# ESP12Proto-V1_0.net
KiCad netlist of a schematic drawn in EAGLE
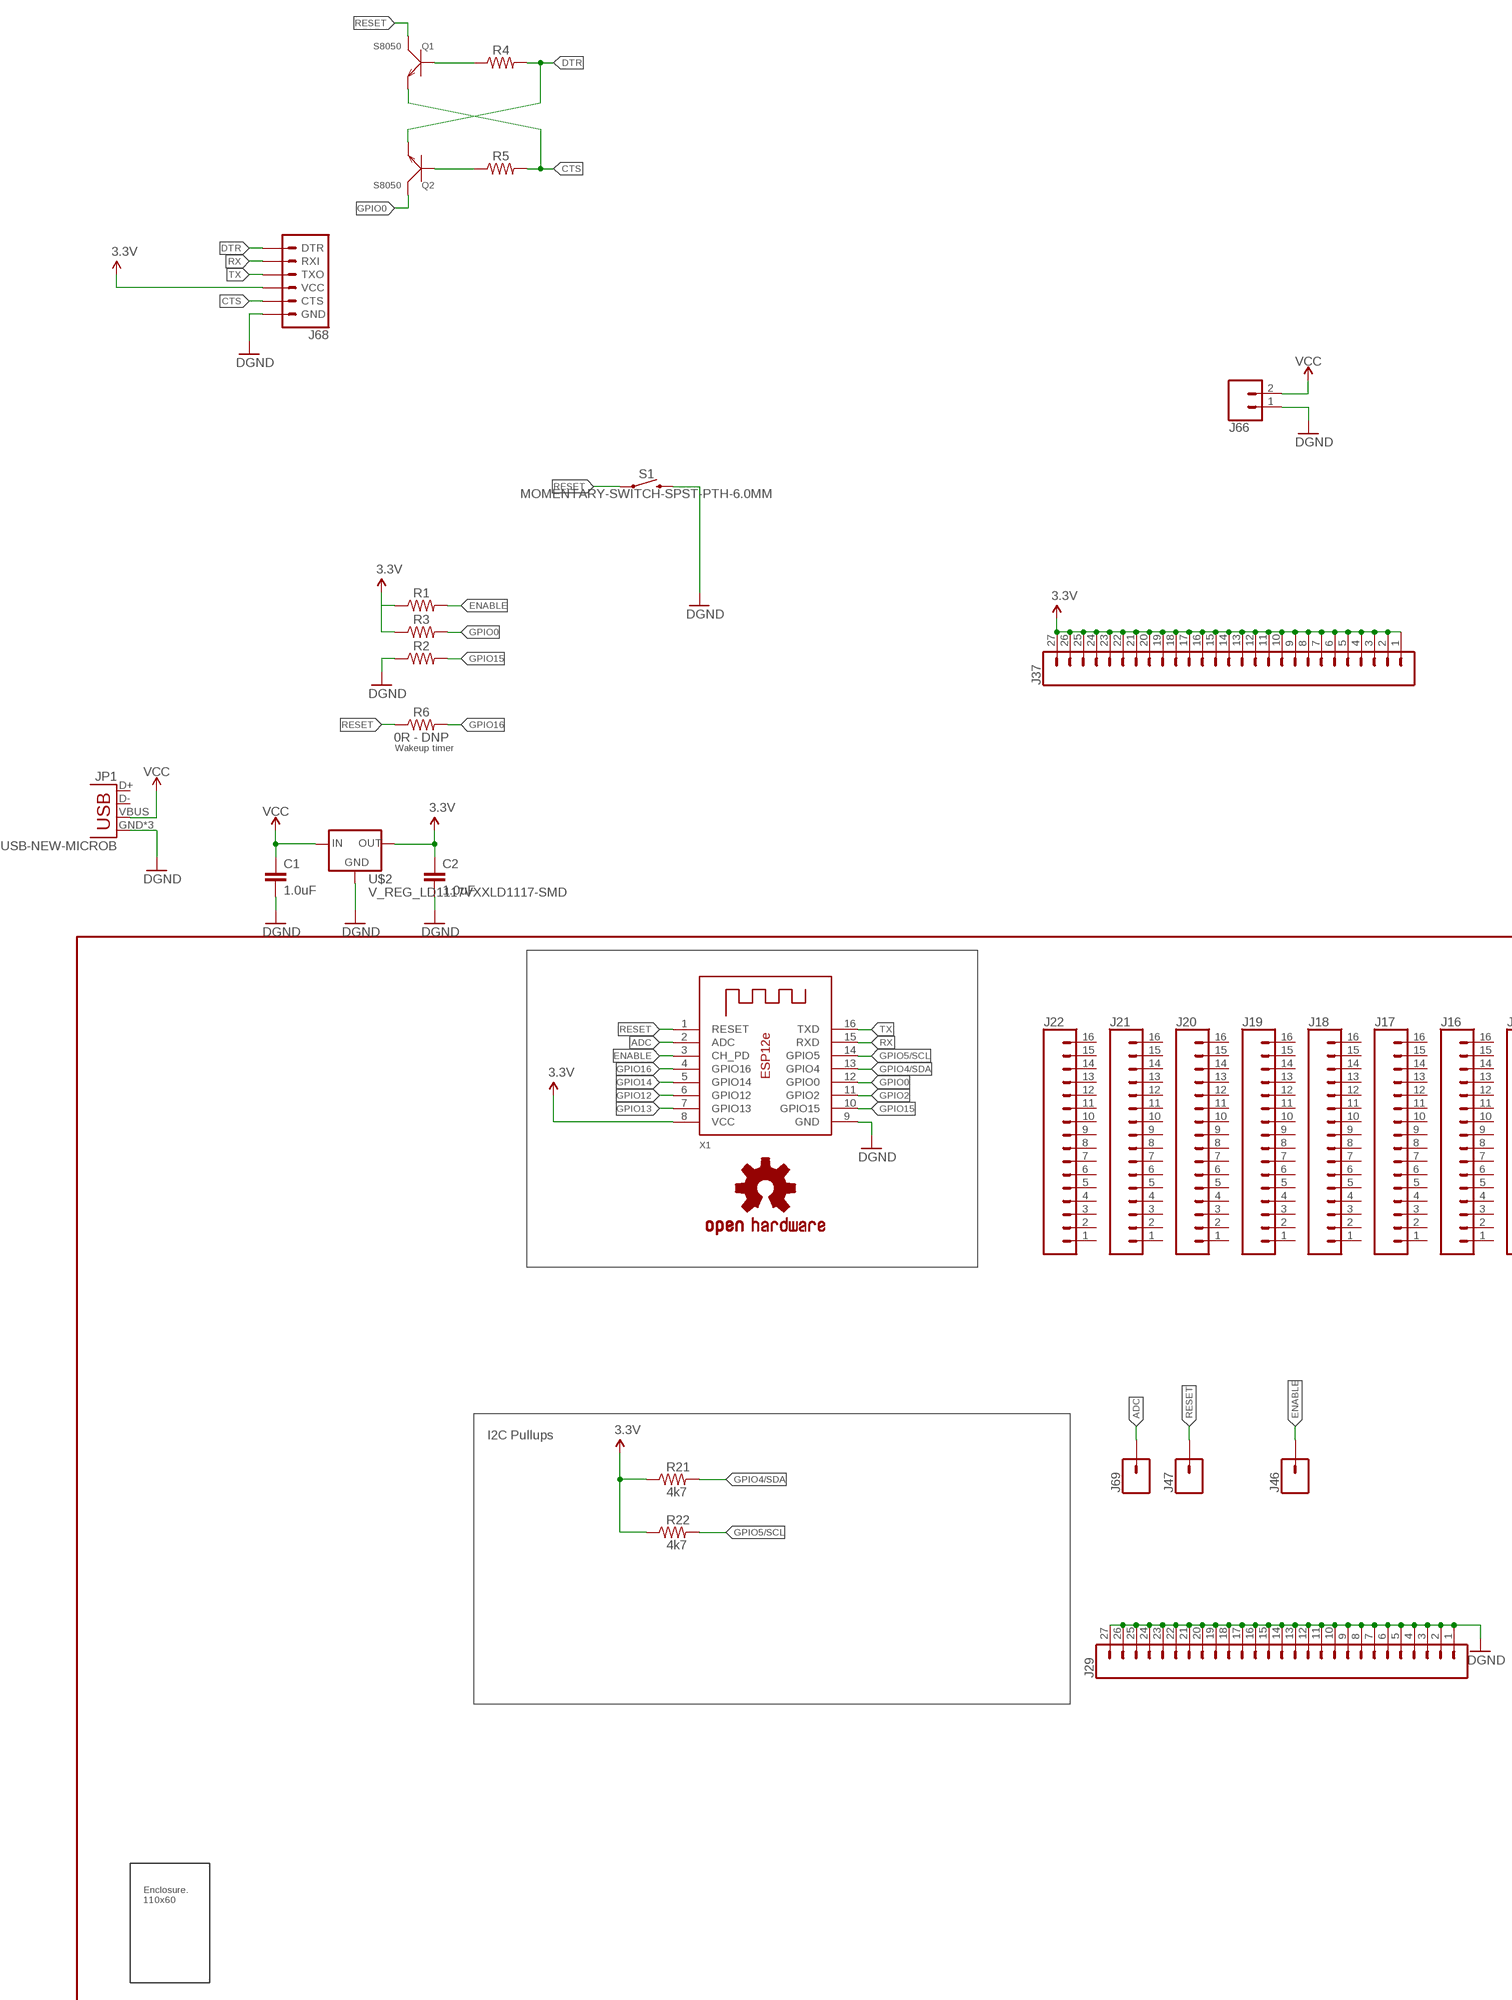
[diagram p0: schematic, sheet 1, part 1 of 2]
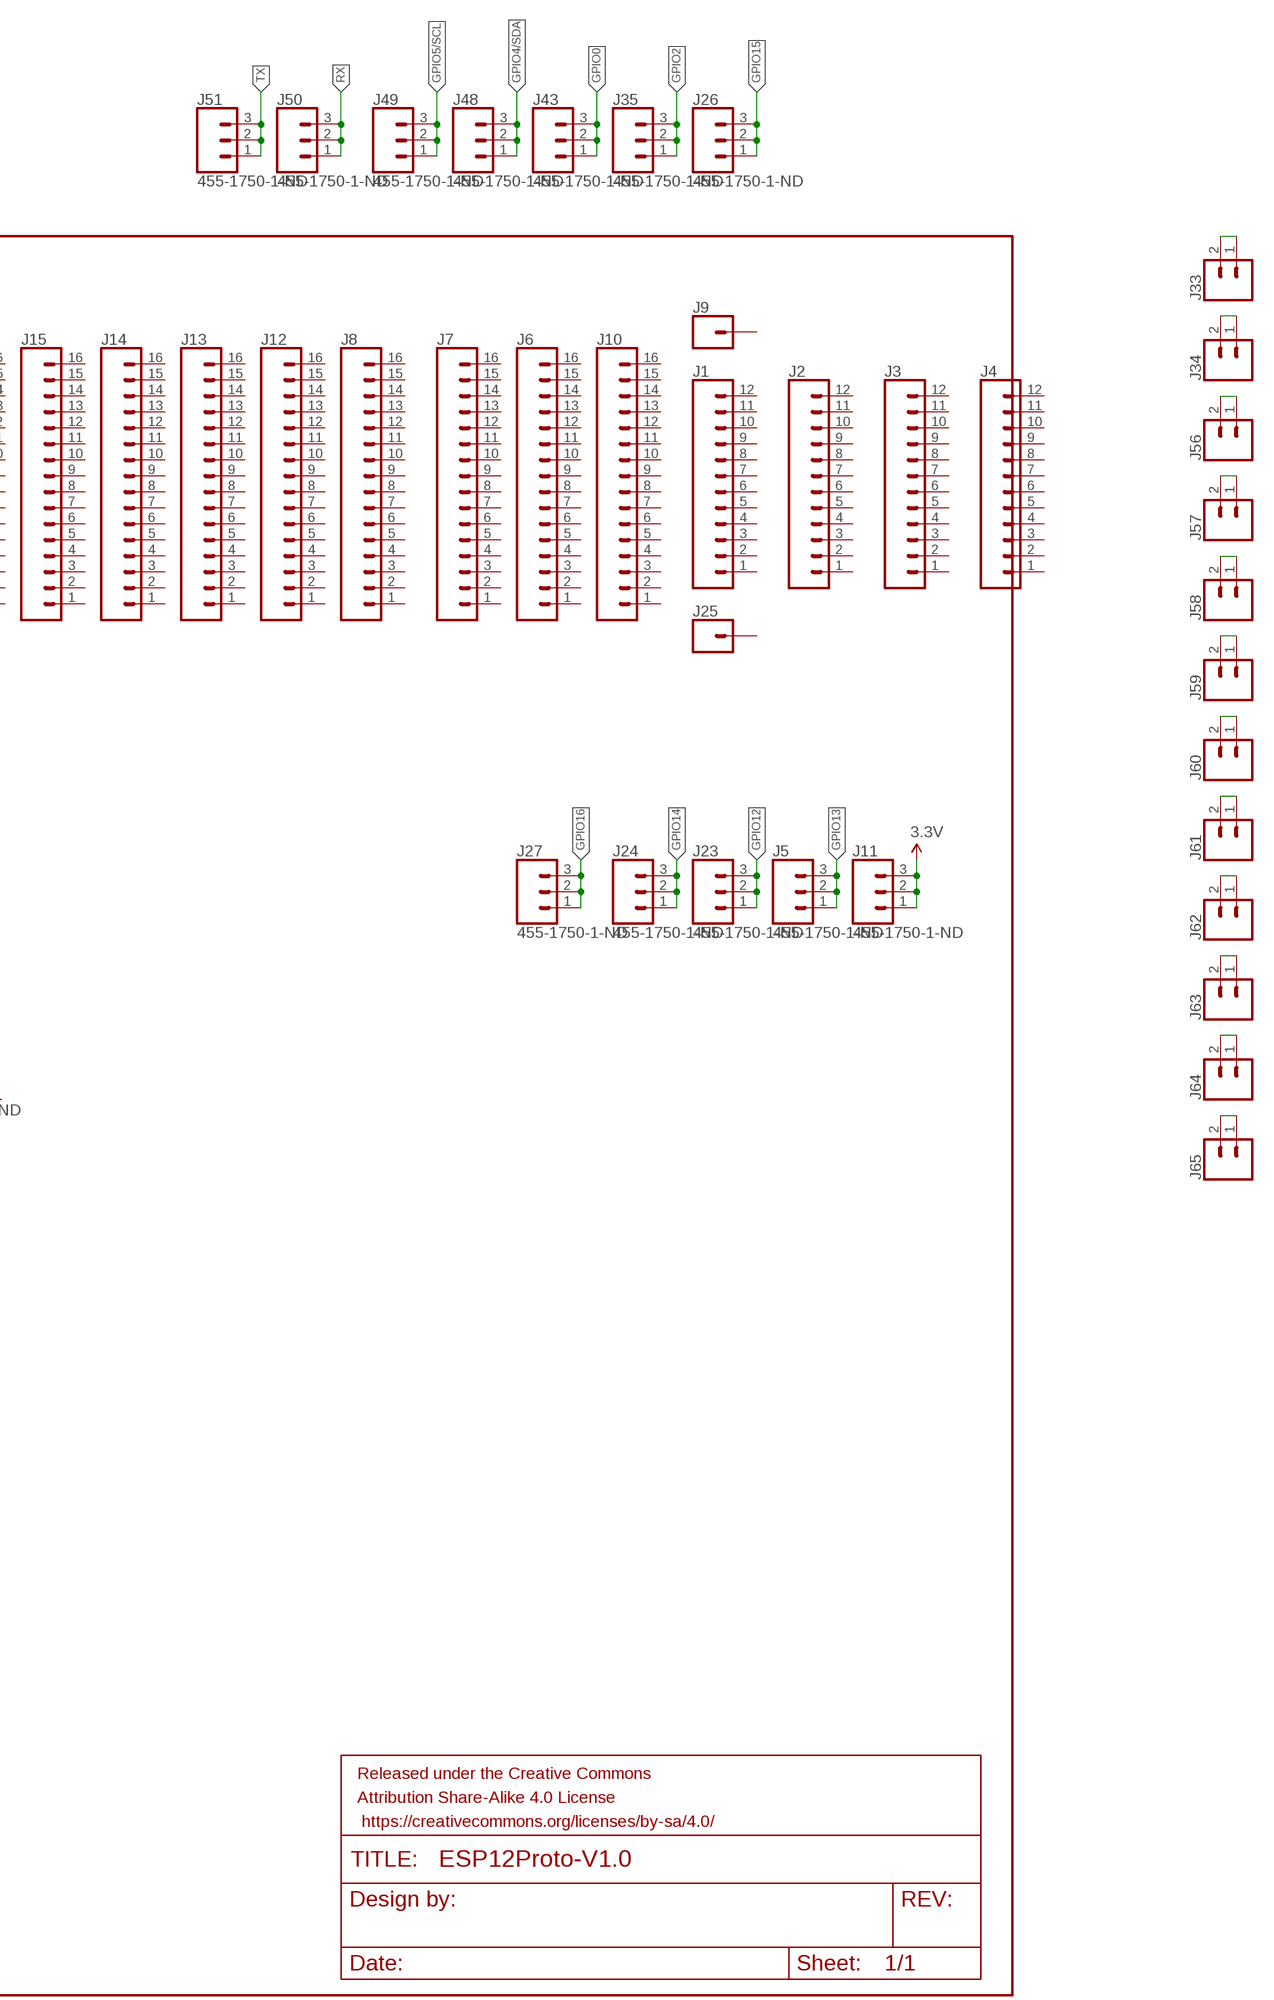
[diagram p1: schematic, sheet 1, part 2 of 2]

(export (version "E")
  (design (tool "Eeschema 10.0.6"))
  (components
    (comp (ref "C1")
      (value "1.0uF")
      (footprint "eagle-import:0805")
      (libsource (lib "eagle-import") (part "1.0UF-0805-25V-10%"))
    )
    (comp (ref "C2")
      (value "1.0uF")
      (footprint "eagle-import:0805")
      (libsource (lib "eagle-import") (part "1.0UF-0805-25V-10%"))
    )
    (comp (ref "FRAME2")
      (value "FRAME-LEDGER")
      (footprint "eagle-import:CREATIVE_COMMONS")
      (libsource (lib "eagle-import") (part "FRAME-LEDGER"))
    )
    (comp (ref "J1")
      (value "CONN_12NO_SILK")
      (footprint "eagle-import:1X12_NO_SILK")
      (libsource (lib "eagle-import") (part "CONN_12NO_SILK"))
    )
    (comp (ref "J2")
      (value "CONN_12NO_SILK")
      (footprint "eagle-import:1X12_NO_SILK")
      (libsource (lib "eagle-import") (part "CONN_12NO_SILK"))
    )
    (comp (ref "J3")
      (value "CONN_12NO_SILK")
      (footprint "eagle-import:1X12_NO_SILK")
      (libsource (lib "eagle-import") (part "CONN_12NO_SILK"))
    )
    (comp (ref "J4")
      (value "CONN_12NO_SILK")
      (footprint "eagle-import:1X12_NO_SILK")
      (libsource (lib "eagle-import") (part "CONN_12NO_SILK"))
    )
    (comp (ref "J5")
      (value "455-1750-1-ND")
      (footprint "eagle-import:1X03")
      (libsource (lib "eagle-import") (part "CONN_03"))
    )
    (comp (ref "J6")
      (value "CONN_161X16_NO_SILK")
      (footprint "eagle-import:1X16_NO_SILK")
      (libsource (lib "eagle-import") (part "CONN_161X16_NO_SILK"))
    )
    (comp (ref "J7")
      (value "CONN_161X16_NO_SILK")
      (footprint "eagle-import:1X16_NO_SILK")
      (libsource (lib "eagle-import") (part "CONN_161X16_NO_SILK"))
    )
    (comp (ref "J8")
      (value "CONN_161X16_NO_SILK")
      (footprint "eagle-import:1X16_NO_SILK")
      (libsource (lib "eagle-import") (part "CONN_161X16_NO_SILK"))
    )
    (comp (ref "J9")
      (value "CONN_01PTH_NO_SILK_YES_STOP")
      (footprint "eagle-import:1X01_NO_SILK")
      (libsource (lib "eagle-import") (part "CONN_01PTH_NO_SILK_YES_STOP"))
    )
    (comp (ref "J10")
      (value "CONN_161X16_NO_SILK")
      (footprint "eagle-import:1X16_NO_SILK")
      (libsource (lib "eagle-import") (part "CONN_161X16_NO_SILK"))
    )
    (comp (ref "J11")
      (value "455-1750-1-ND")
      (footprint "eagle-import:1X03")
      (libsource (lib "eagle-import") (part "CONN_03"))
    )
    (comp (ref "J12")
      (value "CONN_161X16_NO_SILK")
      (footprint "eagle-import:1X16_NO_SILK")
      (libsource (lib "eagle-import") (part "CONN_161X16_NO_SILK"))
    )
    (comp (ref "J13")
      (value "CONN_161X16_NO_SILK")
      (footprint "eagle-import:1X16_NO_SILK")
      (libsource (lib "eagle-import") (part "CONN_161X16_NO_SILK"))
    )
    (comp (ref "J14")
      (value "CONN_161X16_NO_SILK")
      (footprint "eagle-import:1X16_NO_SILK")
      (libsource (lib "eagle-import") (part "CONN_161X16_NO_SILK"))
    )
    (comp (ref "J15")
      (value "CONN_161X16_NO_SILK")
      (footprint "eagle-import:1X16_NO_SILK")
      (libsource (lib "eagle-import") (part "CONN_161X16_NO_SILK"))
    )
    (comp (ref "J16")
      (value "CONN_161X16_NO_SILK")
      (footprint "eagle-import:1X16_NO_SILK")
      (libsource (lib "eagle-import") (part "CONN_161X16_NO_SILK"))
    )
    (comp (ref "J17")
      (value "CONN_161X16_NO_SILK")
      (footprint "eagle-import:1X16_NO_SILK")
      (libsource (lib "eagle-import") (part "CONN_161X16_NO_SILK"))
    )
    (comp (ref "J18")
      (value "CONN_161X16_NO_SILK")
      (footprint "eagle-import:1X16_NO_SILK")
      (libsource (lib "eagle-import") (part "CONN_161X16_NO_SILK"))
    )
    (comp (ref "J19")
      (value "CONN_161X16_NO_SILK")
      (footprint "eagle-import:1X16_NO_SILK")
      (libsource (lib "eagle-import") (part "CONN_161X16_NO_SILK"))
    )
    (comp (ref "J20")
      (value "CONN_161X16_NO_SILK")
      (footprint "eagle-import:1X16_NO_SILK")
      (libsource (lib "eagle-import") (part "CONN_161X16_NO_SILK"))
    )
    (comp (ref "J21")
      (value "CONN_161X16_NO_SILK")
      (footprint "eagle-import:1X16_NO_SILK")
      (libsource (lib "eagle-import") (part "CONN_161X16_NO_SILK"))
    )
    (comp (ref "J22")
      (value "CONN_161X16_NO_SILK")
      (footprint "eagle-import:1X16_NO_SILK")
      (libsource (lib "eagle-import") (part "CONN_161X16_NO_SILK"))
    )
    (comp (ref "J23")
      (value "455-1750-1-ND")
      (footprint "eagle-import:1X03")
      (libsource (lib "eagle-import") (part "CONN_03"))
    )
    (comp (ref "J24")
      (value "455-1750-1-ND")
      (footprint "eagle-import:1X03")
      (libsource (lib "eagle-import") (part "CONN_03"))
    )
    (comp (ref "J25")
      (value "CONN_01PTH_NO_SILK_YES_STOP")
      (footprint "eagle-import:1X01_NO_SILK")
      (libsource (lib "eagle-import") (part "CONN_01PTH_NO_SILK_YES_STOP"))
    )
    (comp (ref "J26")
      (value "455-1750-1-ND")
      (footprint "eagle-import:1X03")
      (libsource (lib "eagle-import") (part "CONN_03"))
    )
    (comp (ref "J27")
      (value "455-1750-1-ND")
      (footprint "eagle-import:1X03")
      (libsource (lib "eagle-import") (part "CONN_03"))
    )
    (comp (ref "J29")
      (value "CONN_27")
      (footprint "eagle-import:1X27")
      (libsource (lib "eagle-import") (part "CONN_27"))
    )
    (comp (ref "J33")
      (value "CONN_02")
      (footprint "eagle-import:1X02")
      (libsource (lib "eagle-import") (part "CONN_02"))
    )
    (comp (ref "J34")
      (value "CONN_02")
      (footprint "eagle-import:1X02")
      (libsource (lib "eagle-import") (part "CONN_02"))
    )
    (comp (ref "J35")
      (value "455-1750-1-ND")
      (footprint "eagle-import:1X03")
      (libsource (lib "eagle-import") (part "CONN_03"))
    )
    (comp (ref "J37")
      (value "CONN_27")
      (footprint "eagle-import:1X27")
      (libsource (lib "eagle-import") (part "CONN_27"))
    )
    (comp (ref "J43")
      (value "455-1750-1-ND")
      (footprint "eagle-import:1X03")
      (libsource (lib "eagle-import") (part "CONN_03"))
    )
    (comp (ref "J46")
      (value "CONN_01PTH_NO_SILK_YES_STOP")
      (footprint "eagle-import:1X01_NO_SILK")
      (libsource (lib "eagle-import") (part "CONN_01PTH_NO_SILK_YES_STOP"))
    )
    (comp (ref "J47")
      (value "CONN_01PTH_NO_SILK_YES_STOP")
      (footprint "eagle-import:1X01_NO_SILK")
      (libsource (lib "eagle-import") (part "CONN_01PTH_NO_SILK_YES_STOP"))
    )
    (comp (ref "J48")
      (value "455-1750-1-ND")
      (footprint "eagle-import:1X03")
      (libsource (lib "eagle-import") (part "CONN_03"))
    )
    (comp (ref "J49")
      (value "455-1750-1-ND")
      (footprint "eagle-import:1X03")
      (libsource (lib "eagle-import") (part "CONN_03"))
    )
    (comp (ref "J50")
      (value "455-1750-1-ND")
      (footprint "eagle-import:1X03")
      (libsource (lib "eagle-import") (part "CONN_03"))
    )
    (comp (ref "J51")
      (value "455-1750-1-ND")
      (footprint "eagle-import:1X03")
      (libsource (lib "eagle-import") (part "CONN_03"))
    )
    (comp (ref "J56")
      (value "CONN_02")
      (footprint "eagle-import:1X02")
      (libsource (lib "eagle-import") (part "CONN_02"))
    )
    (comp (ref "J57")
      (value "CONN_02")
      (footprint "eagle-import:1X02")
      (libsource (lib "eagle-import") (part "CONN_02"))
    )
    (comp (ref "J58")
      (value "CONN_02")
      (footprint "eagle-import:1X02")
      (libsource (lib "eagle-import") (part "CONN_02"))
    )
    (comp (ref "J59")
      (value "CONN_02")
      (footprint "eagle-import:1X02")
      (libsource (lib "eagle-import") (part "CONN_02"))
    )
    (comp (ref "J60")
      (value "CONN_02")
      (footprint "eagle-import:1X02")
      (libsource (lib "eagle-import") (part "CONN_02"))
    )
    (comp (ref "J61")
      (value "CONN_02")
      (footprint "eagle-import:1X02")
      (libsource (lib "eagle-import") (part "CONN_02"))
    )
    (comp (ref "J62")
      (value "CONN_02")
      (footprint "eagle-import:1X02")
      (libsource (lib "eagle-import") (part "CONN_02"))
    )
    (comp (ref "J63")
      (value "CONN_02")
      (footprint "eagle-import:1X02")
      (libsource (lib "eagle-import") (part "CONN_02"))
    )
    (comp (ref "J64")
      (value "CONN_02")
      (footprint "eagle-import:1X02")
      (libsource (lib "eagle-import") (part "CONN_02"))
    )
    (comp (ref "J65")
      (value "CONN_02")
      (footprint "eagle-import:1X02")
      (libsource (lib "eagle-import") (part "CONN_02"))
    )
    (comp (ref "J66")
      (value "CONN_02-JST-2MM-SMT")
      (footprint "eagle-import:JST-2-SMD")
      (libsource (lib "eagle-import") (part "CONN_02-JST-2MM-SMT"))
    )
    (comp (ref "J68")
      (value "6_PIN_SERIAL_TARGETSILK")
      (footprint "eagle-import:6_PIN_SERIAL_TARGET_SIDE_W_SILK")
      (libsource (lib "eagle-import") (part "6_PIN_SERIAL_TARGETSILK"))
    )
    (comp (ref "J69")
      (value "CONN_01PTH_NO_SILK_YES_STOP")
      (footprint "eagle-import:1X01_NO_SILK")
      (libsource (lib "eagle-import") (part "CONN_01PTH_NO_SILK_YES_STOP"))
    )
    (comp (ref "JP1")
      (value "USB-NEW-MICROB")
      (footprint "eagle-import:USB-MICROB")
      (libsource (lib "eagle-import") (part "USB-NEW-MICROB"))
    )
    (comp (ref "LOGO1")
      (value "OSHW-LOGOM")
      (footprint "eagle-import:OSHW-LOGO-M")
      (libsource (lib "eagle-import") (part "OSHW-LOGOM"))
    )
    (comp (ref "Q1")
      (value "S8050")
      (footprint "eagle-import:SOT-23")
      (libsource (lib "eagle-import") (part "SMD-TRANSISTORS-NPN-25V-500MW-S8050(SOT-23)"))
    )
    (comp (ref "Q2")
      (value "S8050")
      (footprint "eagle-import:SOT-23")
      (libsource (lib "eagle-import") (part "SMD-TRANSISTORS-NPN-25V-500MW-S8050(SOT-23)"))
    )
    (comp (ref "R1")
      (value "RESISTOR0805")
      (footprint "eagle-import:0805")
      (libsource (lib "eagle-import") (part "RESISTOR0805"))
    )
    (comp (ref "R2")
      (value "RESISTOR0805")
      (footprint "eagle-import:0805")
      (libsource (lib "eagle-import") (part "RESISTOR0805"))
    )
    (comp (ref "R3")
      (value "RESISTOR0805")
      (footprint "eagle-import:0805")
      (libsource (lib "eagle-import") (part "RESISTOR0805"))
    )
    (comp (ref "R4")
      (value "RESISTOR0805")
      (footprint "eagle-import:0805")
      (libsource (lib "eagle-import") (part "RESISTOR0805"))
    )
    (comp (ref "R5")
      (value "RESISTOR0805")
      (footprint "eagle-import:0805")
      (libsource (lib "eagle-import") (part "RESISTOR0805"))
    )
    (comp (ref "R6")
      (value "0R - DNP")
      (footprint "eagle-import:0805")
      (libsource (lib "eagle-import") (part "RESISTOR0805"))
    )
    (comp (ref "R21")
      (value "4k7")
      (footprint "eagle-import:0805")
      (libsource (lib "eagle-import") (part "RESISTOR0805"))
    )
    (comp (ref "R22")
      (value "4k7")
      (footprint "eagle-import:0805")
      (libsource (lib "eagle-import") (part "RESISTOR0805"))
    )
    (comp (ref "S1")
      (value "MOMENTARY-SWITCH-SPST-PTH-6.0MM")
      (footprint "eagle-import:TACTILE_SWITCH_PTH_6.0MM")
      (libsource (lib "eagle-import") (part "MOMENTARY-SWITCH-SPST-PTH-6.0MM"))
    )
    (comp (ref "U$1")
      (value "CAMDENBOSS-ENCLOSURE-110X60BOTH-EXTENDED-WIDE")
      (footprint "eagle-import:CAMDENBOSS_ENCLOSURE_110X60_WIDE_EXTENDED")
      (libsource (lib "eagle-import") (part "CAMDENBOSS-ENCLOSURE-110X60BOTH-EXTENDED-WIDE"))
    )
    (comp (ref "U$2")
      (value "V_REG_LD1117VXXLD1117-SMD")
      (footprint "eagle-import:SOT223")
      (libsource (lib "eagle-import") (part "V_REG_LD1117VXXLD1117-SMD"))
    )
    (comp (ref "X1")
      (value "ESP-12E")
      (footprint "eagle-import:ESP-12E")
      (libsource (lib "eagle-import") (part "ESP-12E"))
    )
  )
  (nets
    (net (code "1") (name "3.3V") (class "Default")
      (node (ref "C2") (pin "1") (pinfunction "1_1") (pintype "passive"))
      (node (ref "J11") (pin "1") (pinfunction "1_1") (pintype "passive"))
      (node (ref "J11") (pin "2") (pinfunction "2_2") (pintype "passive"))
      (node (ref "J11") (pin "3") (pinfunction "3_3") (pintype "passive"))
      (node (ref "J37") (pin "1") (pinfunction "1_1") (pintype "passive"))
      (node (ref "J37") (pin "10") (pinfunction "10_10") (pintype "passive"))
      (node (ref "J37") (pin "11") (pinfunction "11_11") (pintype "passive"))
      (node (ref "J37") (pin "12") (pinfunction "12_12") (pintype "passive"))
      (node (ref "J37") (pin "13") (pinfunction "13_13") (pintype "passive"))
      (node (ref "J37") (pin "14") (pinfunction "14_14") (pintype "passive"))
      (node (ref "J37") (pin "15") (pinfunction "15_15") (pintype "passive"))
      (node (ref "J37") (pin "16") (pinfunction "16_16") (pintype "passive"))
      (node (ref "J37") (pin "17") (pinfunction "17_17") (pintype "passive"))
      (node (ref "J37") (pin "18") (pinfunction "18_18") (pintype "passive"))
      (node (ref "J37") (pin "19") (pinfunction "19_19") (pintype "passive"))
      (node (ref "J37") (pin "2") (pinfunction "2_2") (pintype "passive"))
      (node (ref "J37") (pin "20") (pinfunction "20_20") (pintype "passive"))
      (node (ref "J37") (pin "21") (pinfunction "21_21") (pintype "passive"))
      (node (ref "J37") (pin "22") (pinfunction "22_22") (pintype "passive"))
      (node (ref "J37") (pin "23") (pinfunction "23_23") (pintype "passive"))
      (node (ref "J37") (pin "24") (pinfunction "24_24") (pintype "passive"))
      (node (ref "J37") (pin "25") (pinfunction "25_25") (pintype "passive"))
      (node (ref "J37") (pin "26") (pinfunction "26_26") (pintype "passive"))
      (node (ref "J37") (pin "27") (pinfunction "27_27") (pintype "passive"))
      (node (ref "J37") (pin "3") (pinfunction "3_3") (pintype "passive"))
      (node (ref "J37") (pin "4") (pinfunction "4_4") (pintype "passive"))
      (node (ref "J37") (pin "5") (pinfunction "5_5") (pintype "passive"))
      (node (ref "J37") (pin "6") (pinfunction "6_6") (pintype "passive"))
      (node (ref "J37") (pin "7") (pinfunction "7_7") (pintype "passive"))
      (node (ref "J37") (pin "8") (pinfunction "8_8") (pintype "passive"))
      (node (ref "J37") (pin "9") (pinfunction "9_9") (pintype "passive"))
      (node (ref "J68") (pin "P$4") (pinfunction "VCC_P$4") (pintype "passive"))
      (node (ref "R1") (pin "1") (pinfunction "1_1") (pintype "passive"))
      (node (ref "R21") (pin "1") (pinfunction "1_1") (pintype "passive"))
      (node (ref "R22") (pin "1") (pinfunction "1_1") (pintype "passive"))
      (node (ref "R3") (pin "1") (pinfunction "1_1") (pintype "passive"))
      (node (ref "U$2") (pin "2") (pinfunction "OUT_2") (pintype "passive"))
      (node (ref "X1") (pin "8") (pinfunction "VCC_8") (pintype "power_in"))
    )
    (net (code "2") (name "ADC") (class "Default")
      (node (ref "J69") (pin "1") (pinfunction "1_1") (pintype "passive"))
      (node (ref "X1") (pin "2") (pinfunction "ADC_2") (pintype "passive"))
    )
    (net (code "3") (name "CTS") (class "Default")
      (node (ref "J68") (pin "P$5") (pinfunction "CTS_P$5") (pintype "passive"))
      (node (ref "Q1") (pin "2") (pinfunction "E_2") (pintype "passive"))
      (node (ref "R5") (pin "2") (pinfunction "2_2") (pintype "passive"))
    )
    (net (code "4") (name "DGND") (class "Default")
      (node (ref "C1") (pin "2") (pinfunction "2_2") (pintype "passive"))
      (node (ref "C2") (pin "2") (pinfunction "2_2") (pintype "passive"))
      (node (ref "J29") (pin "1") (pinfunction "1_1") (pintype "passive"))
      (node (ref "J29") (pin "10") (pinfunction "10_10") (pintype "passive"))
      (node (ref "J29") (pin "11") (pinfunction "11_11") (pintype "passive"))
      (node (ref "J29") (pin "12") (pinfunction "12_12") (pintype "passive"))
      (node (ref "J29") (pin "13") (pinfunction "13_13") (pintype "passive"))
      (node (ref "J29") (pin "14") (pinfunction "14_14") (pintype "passive"))
      (node (ref "J29") (pin "15") (pinfunction "15_15") (pintype "passive"))
      (node (ref "J29") (pin "16") (pinfunction "16_16") (pintype "passive"))
      (node (ref "J29") (pin "17") (pinfunction "17_17") (pintype "passive"))
      (node (ref "J29") (pin "18") (pinfunction "18_18") (pintype "passive"))
      (node (ref "J29") (pin "19") (pinfunction "19_19") (pintype "passive"))
      (node (ref "J29") (pin "2") (pinfunction "2_2") (pintype "passive"))
      (node (ref "J29") (pin "20") (pinfunction "20_20") (pintype "passive"))
      (node (ref "J29") (pin "21") (pinfunction "21_21") (pintype "passive"))
      (node (ref "J29") (pin "22") (pinfunction "22_22") (pintype "passive"))
      (node (ref "J29") (pin "23") (pinfunction "23_23") (pintype "passive"))
      (node (ref "J29") (pin "24") (pinfunction "24_24") (pintype "passive"))
      (node (ref "J29") (pin "25") (pinfunction "25_25") (pintype "passive"))
      (node (ref "J29") (pin "26") (pinfunction "26_26") (pintype "passive"))
      (node (ref "J29") (pin "27") (pinfunction "27_27") (pintype "passive"))
      (node (ref "J29") (pin "3") (pinfunction "3_3") (pintype "passive"))
      (node (ref "J29") (pin "4") (pinfunction "4_4") (pintype "passive"))
      (node (ref "J29") (pin "5") (pinfunction "5_5") (pintype "passive"))
      (node (ref "J29") (pin "6") (pinfunction "6_6") (pintype "passive"))
      (node (ref "J29") (pin "7") (pinfunction "7_7") (pintype "passive"))
      (node (ref "J29") (pin "8") (pinfunction "8_8") (pintype "passive"))
      (node (ref "J29") (pin "9") (pinfunction "9_9") (pintype "passive"))
      (node (ref "J66") (pin "1") (pinfunction "2_1") (pintype "passive"))
      (node (ref "J68") (pin "P$6") (pinfunction "GND_P$6") (pintype "passive"))
      (node (ref "JP1") (pin "GND") (pinfunction "GND_GND") (pintype "bidirectional"))
      (node (ref "JP1") (pin "MT1") (pinfunction "GND_MT1") (pintype "bidirectional"))
      (node (ref "JP1") (pin "MT2") (pinfunction "GND_MT2") (pintype "bidirectional"))
      (node (ref "R2") (pin "1") (pinfunction "1_1") (pintype "passive"))
      (node (ref "S1") (pin "3") (pinfunction "2_3") (pintype "passive"))
      (node (ref "U$2") (pin "1") (pinfunction "GND_1") (pintype "input"))
      (node (ref "X1") (pin "9") (pinfunction "GND_9") (pintype "power_in"))
    )
    (net (code "5") (name "DTR") (class "Default")
      (node (ref "J68") (pin "P$1") (pinfunction "DTR_P$1") (pintype "passive"))
      (node (ref "Q2") (pin "2") (pinfunction "E_2") (pintype "passive"))
      (node (ref "R4") (pin "2") (pinfunction "2_2") (pintype "passive"))
    )
    (net (code "6") (name "ENABLE") (class "Default")
      (node (ref "J46") (pin "1") (pinfunction "1_1") (pintype "passive"))
      (node (ref "R1") (pin "2") (pinfunction "2_2") (pintype "passive"))
      (node (ref "X1") (pin "3") (pinfunction "CH_PD_3") (pintype "input"))
    )
    (net (code "7") (name "GPIO0") (class "Default")
      (node (ref "J43") (pin "1") (pinfunction "1_1") (pintype "passive"))
      (node (ref "J43") (pin "2") (pinfunction "2_2") (pintype "passive"))
      (node (ref "J43") (pin "3") (pinfunction "3_3") (pintype "passive"))
      (node (ref "Q2") (pin "3") (pinfunction "C_3") (pintype "passive"))
      (node (ref "R3") (pin "2") (pinfunction "2_2") (pintype "passive"))
      (node (ref "X1") (pin "12") (pinfunction "GPIO0_12") (pintype "bidirectional"))
    )
    (net (code "8") (name "GPIO2") (class "Default")
      (node (ref "J35") (pin "1") (pinfunction "1_1") (pintype "passive"))
      (node (ref "J35") (pin "2") (pinfunction "2_2") (pintype "passive"))
      (node (ref "J35") (pin "3") (pinfunction "3_3") (pintype "passive"))
      (node (ref "X1") (pin "11") (pinfunction "GPIO2_11") (pintype "bidirectional"))
    )
    (net (code "9") (name "GPIO4{slash}SDA") (class "Default")
      (node (ref "J48") (pin "1") (pinfunction "1_1") (pintype "passive"))
      (node (ref "J48") (pin "2") (pinfunction "2_2") (pintype "passive"))
      (node (ref "J48") (pin "3") (pinfunction "3_3") (pintype "passive"))
      (node (ref "R21") (pin "2") (pinfunction "2_2") (pintype "passive"))
      (node (ref "X1") (pin "13") (pinfunction "GPIO4_13") (pintype "bidirectional"))
    )
    (net (code "10") (name "GPIO5{slash}SCL") (class "Default")
      (node (ref "J49") (pin "1") (pinfunction "1_1") (pintype "passive"))
      (node (ref "J49") (pin "2") (pinfunction "2_2") (pintype "passive"))
      (node (ref "J49") (pin "3") (pinfunction "3_3") (pintype "passive"))
      (node (ref "R22") (pin "2") (pinfunction "2_2") (pintype "passive"))
      (node (ref "X1") (pin "14") (pinfunction "GPIO5_14") (pintype "bidirectional"))
    )
    (net (code "11") (name "GPIO12") (class "Default")
      (node (ref "J23") (pin "1") (pinfunction "1_1") (pintype "passive"))
      (node (ref "J23") (pin "2") (pinfunction "2_2") (pintype "passive"))
      (node (ref "J23") (pin "3") (pinfunction "3_3") (pintype "passive"))
      (node (ref "X1") (pin "6") (pinfunction "GPIO12_6") (pintype "bidirectional"))
    )
    (net (code "12") (name "GPIO13") (class "Default")
      (node (ref "J5") (pin "1") (pinfunction "1_1") (pintype "passive"))
      (node (ref "J5") (pin "2") (pinfunction "2_2") (pintype "passive"))
      (node (ref "J5") (pin "3") (pinfunction "3_3") (pintype "passive"))
      (node (ref "X1") (pin "7") (pinfunction "GPIO13_7") (pintype "bidirectional"))
    )
    (net (code "13") (name "GPIO14") (class "Default")
      (node (ref "J24") (pin "1") (pinfunction "1_1") (pintype "passive"))
      (node (ref "J24") (pin "2") (pinfunction "2_2") (pintype "passive"))
      (node (ref "J24") (pin "3") (pinfunction "3_3") (pintype "passive"))
      (node (ref "X1") (pin "5") (pinfunction "GPIO14_5") (pintype "bidirectional"))
    )
    (net (code "14") (name "GPIO15") (class "Default")
      (node (ref "J26") (pin "1") (pinfunction "1_1") (pintype "passive"))
      (node (ref "J26") (pin "2") (pinfunction "2_2") (pintype "passive"))
      (node (ref "J26") (pin "3") (pinfunction "3_3") (pintype "passive"))
      (node (ref "R2") (pin "2") (pinfunction "2_2") (pintype "passive"))
      (node (ref "X1") (pin "10") (pinfunction "GPIO15_10") (pintype "bidirectional"))
    )
    (net (code "15") (name "GPIO16") (class "Default")
      (node (ref "J27") (pin "1") (pinfunction "1_1") (pintype "passive"))
      (node (ref "J27") (pin "2") (pinfunction "2_2") (pintype "passive"))
      (node (ref "J27") (pin "3") (pinfunction "3_3") (pintype "passive"))
      (node (ref "R6") (pin "2") (pinfunction "2_2") (pintype "passive"))
      (node (ref "X1") (pin "4") (pinfunction "GPIO16_4") (pintype "bidirectional"))
    )
    (net (code "16") (name "Net-(J33-Pad1)") (class "Default")
      (node (ref "J33") (pin "1") (pinfunction "1_1") (pintype "passive"))
      (node (ref "J33") (pin "2") (pinfunction "2_2") (pintype "passive"))
    )
    (net (code "17") (name "Net-(J34-Pad1)") (class "Default")
      (node (ref "J34") (pin "1") (pinfunction "1_1") (pintype "passive"))
      (node (ref "J34") (pin "2") (pinfunction "2_2") (pintype "passive"))
    )
    (net (code "18") (name "Net-(J56-Pad1)") (class "Default")
      (node (ref "J56") (pin "1") (pinfunction "1_1") (pintype "passive"))
      (node (ref "J56") (pin "2") (pinfunction "2_2") (pintype "passive"))
    )
    (net (code "19") (name "Net-(J57-Pad1)") (class "Default")
      (node (ref "J57") (pin "1") (pinfunction "1_1") (pintype "passive"))
      (node (ref "J57") (pin "2") (pinfunction "2_2") (pintype "passive"))
    )
    (net (code "20") (name "Net-(J58-Pad1)") (class "Default")
      (node (ref "J58") (pin "1") (pinfunction "1_1") (pintype "passive"))
      (node (ref "J58") (pin "2") (pinfunction "2_2") (pintype "passive"))
    )
    (net (code "21") (name "Net-(J59-Pad1)") (class "Default")
      (node (ref "J59") (pin "1") (pinfunction "1_1") (pintype "passive"))
      (node (ref "J59") (pin "2") (pinfunction "2_2") (pintype "passive"))
    )
    (net (code "22") (name "Net-(J60-Pad1)") (class "Default")
      (node (ref "J60") (pin "1") (pinfunction "1_1") (pintype "passive"))
      (node (ref "J60") (pin "2") (pinfunction "2_2") (pintype "passive"))
    )
    (net (code "23") (name "Net-(J61-Pad1)") (class "Default")
      (node (ref "J61") (pin "1") (pinfunction "1_1") (pintype "passive"))
      (node (ref "J61") (pin "2") (pinfunction "2_2") (pintype "passive"))
    )
    (net (code "24") (name "Net-(J62-Pad1)") (class "Default")
      (node (ref "J62") (pin "1") (pinfunction "1_1") (pintype "passive"))
      (node (ref "J62") (pin "2") (pinfunction "2_2") (pintype "passive"))
    )
    (net (code "25") (name "Net-(J63-Pad1)") (class "Default")
      (node (ref "J63") (pin "1") (pinfunction "1_1") (pintype "passive"))
      (node (ref "J63") (pin "2") (pinfunction "2_2") (pintype "passive"))
    )
    (net (code "26") (name "Net-(J64-Pad1)") (class "Default")
      (node (ref "J64") (pin "1") (pinfunction "1_1") (pintype "passive"))
      (node (ref "J64") (pin "2") (pinfunction "2_2") (pintype "passive"))
    )
    (net (code "27") (name "Net-(J65-Pad1)") (class "Default")
      (node (ref "J65") (pin "1") (pinfunction "1_1") (pintype "passive"))
      (node (ref "J65") (pin "2") (pinfunction "2_2") (pintype "passive"))
    )
    (net (code "28") (name "Net-(Q1-B)") (class "Default")
      (node (ref "Q1") (pin "1") (pinfunction "B_1") (pintype "passive"))
      (node (ref "R4") (pin "1") (pinfunction "1_1") (pintype "passive"))
    )
    (net (code "29") (name "Net-(Q2-B)") (class "Default")
      (node (ref "Q2") (pin "1") (pinfunction "B_1") (pintype "passive"))
      (node (ref "R5") (pin "1") (pinfunction "1_1") (pintype "passive"))
    )
    (net (code "30") (name "RESET") (class "Default")
      (node (ref "J47") (pin "1") (pinfunction "1_1") (pintype "passive"))
      (node (ref "Q1") (pin "3") (pinfunction "C_3") (pintype "passive"))
      (node (ref "R6") (pin "1") (pinfunction "1_1") (pintype "passive"))
      (node (ref "S1") (pin "1") (pinfunction "1_1") (pintype "passive"))
      (node (ref "X1") (pin "1") (pinfunction "RESET_1") (pintype "input"))
    )
    (net (code "31") (name "RX") (class "Default")
      (node (ref "J50") (pin "1") (pinfunction "1_1") (pintype "passive"))
      (node (ref "J50") (pin "2") (pinfunction "2_2") (pintype "passive"))
      (node (ref "J50") (pin "3") (pinfunction "3_3") (pintype "passive"))
      (node (ref "J68") (pin "P$3") (pinfunction "RXI_P$3") (pintype "passive"))
      (node (ref "X1") (pin "15") (pinfunction "RXD_15") (pintype "input"))
    )
    (net (code "32") (name "TX") (class "Default")
      (node (ref "J51") (pin "1") (pinfunction "1_1") (pintype "passive"))
      (node (ref "J51") (pin "2") (pinfunction "2_2") (pintype "passive"))
      (node (ref "J51") (pin "3") (pinfunction "3_3") (pintype "passive"))
      (node (ref "J68") (pin "P$2") (pinfunction "TXO_P$2") (pintype "passive"))
      (node (ref "X1") (pin "16") (pinfunction "TXD_16") (pintype "output"))
    )
    (net (code "33") (name "VCC") (class "Default")
      (node (ref "C1") (pin "1") (pinfunction "1_1") (pintype "passive"))
      (node (ref "J66") (pin "2") (pinfunction "1_2") (pintype "passive"))
      (node (ref "JP1") (pin "VBUS") (pinfunction "VBUS_VBUS") (pintype "bidirectional"))
      (node (ref "U$2") (pin "3") (pinfunction "IN_3") (pintype "input"))
    )
    (net (code "34") (name "unconnected-(J1-Pad1)") (class "Default")
      (node (ref "J1") (pin "1") (pinfunction "1_1") (pintype "passive"))
    )
    (net (code "35") (name "unconnected-(J1-Pad2)") (class "Default")
      (node (ref "J1") (pin "2") (pinfunction "2_2") (pintype "passive"))
    )
    (net (code "36") (name "unconnected-(J1-Pad3)") (class "Default")
      (node (ref "J1") (pin "3") (pinfunction "3_3") (pintype "passive"))
    )
    (net (code "37") (name "unconnected-(J1-Pad4)") (class "Default")
      (node (ref "J1") (pin "4") (pinfunction "4_4") (pintype "passive"))
    )
    (net (code "38") (name "unconnected-(J1-Pad5)") (class "Default")
      (node (ref "J1") (pin "5") (pinfunction "5_5") (pintype "passive"))
    )
    (net (code "39") (name "unconnected-(J1-Pad6)") (class "Default")
      (node (ref "J1") (pin "6") (pinfunction "6_6") (pintype "passive"))
    )
    (net (code "40") (name "unconnected-(J1-Pad7)") (class "Default")
      (node (ref "J1") (pin "7") (pinfunction "7_7") (pintype "passive"))
    )
    (net (code "41") (name "unconnected-(J1-Pad8)") (class "Default")
      (node (ref "J1") (pin "8") (pinfunction "8_8") (pintype "passive"))
    )
    (net (code "42") (name "unconnected-(J1-Pad9)") (class "Default")
      (node (ref "J1") (pin "9") (pinfunction "9_9") (pintype "passive"))
    )
    (net (code "43") (name "unconnected-(J1-Pad10)") (class "Default")
      (node (ref "J1") (pin "10") (pinfunction "10_10") (pintype "passive"))
    )
    (net (code "44") (name "unconnected-(J1-Pad11)") (class "Default")
      (node (ref "J1") (pin "11") (pinfunction "11_11") (pintype "passive"))
    )
    (net (code "45") (name "unconnected-(J1-Pad12)") (class "Default")
      (node (ref "J1") (pin "12") (pinfunction "12_12") (pintype "passive"))
    )
    (net (code "46") (name "unconnected-(J2-Pad1)") (class "Default")
      (node (ref "J2") (pin "1") (pinfunction "1_1") (pintype "passive"))
    )
    (net (code "47") (name "unconnected-(J2-Pad2)") (class "Default")
      (node (ref "J2") (pin "2") (pinfunction "2_2") (pintype "passive"))
    )
    (net (code "48") (name "unconnected-(J2-Pad3)") (class "Default")
      (node (ref "J2") (pin "3") (pinfunction "3_3") (pintype "passive"))
    )
    (net (code "49") (name "unconnected-(J2-Pad4)") (class "Default")
      (node (ref "J2") (pin "4") (pinfunction "4_4") (pintype "passive"))
    )
    (net (code "50") (name "unconnected-(J2-Pad5)") (class "Default")
      (node (ref "J2") (pin "5") (pinfunction "5_5") (pintype "passive"))
    )
    (net (code "51") (name "unconnected-(J2-Pad6)") (class "Default")
      (node (ref "J2") (pin "6") (pinfunction "6_6") (pintype "passive"))
    )
    (net (code "52") (name "unconnected-(J2-Pad7)") (class "Default")
      (node (ref "J2") (pin "7") (pinfunction "7_7") (pintype "passive"))
    )
    (net (code "53") (name "unconnected-(J2-Pad8)") (class "Default")
      (node (ref "J2") (pin "8") (pinfunction "8_8") (pintype "passive"))
    )
    (net (code "54") (name "unconnected-(J2-Pad9)") (class "Default")
      (node (ref "J2") (pin "9") (pinfunction "9_9") (pintype "passive"))
    )
    (net (code "55") (name "unconnected-(J2-Pad10)") (class "Default")
      (node (ref "J2") (pin "10") (pinfunction "10_10") (pintype "passive"))
    )
    (net (code "56") (name "unconnected-(J2-Pad11)") (class "Default")
      (node (ref "J2") (pin "11") (pinfunction "11_11") (pintype "passive"))
    )
    (net (code "57") (name "unconnected-(J2-Pad12)") (class "Default")
      (node (ref "J2") (pin "12") (pinfunction "12_12") (pintype "passive"))
    )
    (net (code "58") (name "unconnected-(J3-Pad1)") (class "Default")
      (node (ref "J3") (pin "1") (pinfunction "1_1") (pintype "passive"))
    )
    (net (code "59") (name "unconnected-(J3-Pad2)") (class "Default")
      (node (ref "J3") (pin "2") (pinfunction "2_2") (pintype "passive"))
    )
    (net (code "60") (name "unconnected-(J3-Pad3)") (class "Default")
      (node (ref "J3") (pin "3") (pinfunction "3_3") (pintype "passive"))
    )
    (net (code "61") (name "unconnected-(J3-Pad4)") (class "Default")
      (node (ref "J3") (pin "4") (pinfunction "4_4") (pintype "passive"))
    )
    (net (code "62") (name "unconnected-(J3-Pad5)") (class "Default")
      (node (ref "J3") (pin "5") (pinfunction "5_5") (pintype "passive"))
    )
    (net (code "63") (name "unconnected-(J3-Pad6)") (class "Default")
      (node (ref "J3") (pin "6") (pinfunction "6_6") (pintype "passive"))
    )
    (net (code "64") (name "unconnected-(J3-Pad7)") (class "Default")
      (node (ref "J3") (pin "7") (pinfunction "7_7") (pintype "passive"))
    )
    (net (code "65") (name "unconnected-(J3-Pad8)") (class "Default")
      (node (ref "J3") (pin "8") (pinfunction "8_8") (pintype "passive"))
    )
    (net (code "66") (name "unconnected-(J3-Pad9)") (class "Default")
      (node (ref "J3") (pin "9") (pinfunction "9_9") (pintype "passive"))
    )
    (net (code "67") (name "unconnected-(J3-Pad10)") (class "Default")
      (node (ref "J3") (pin "10") (pinfunction "10_10") (pintype "passive"))
    )
    (net (code "68") (name "unconnected-(J3-Pad11)") (class "Default")
      (node (ref "J3") (pin "11") (pinfunction "11_11") (pintype "passive"))
    )
    (net (code "69") (name "unconnected-(J3-Pad12)") (class "Default")
      (node (ref "J3") (pin "12") (pinfunction "12_12") (pintype "passive"))
    )
    (net (code "70") (name "unconnected-(J4-Pad1)") (class "Default")
      (node (ref "J4") (pin "1") (pinfunction "1_1") (pintype "passive"))
    )
    (net (code "71") (name "unconnected-(J4-Pad2)") (class "Default")
      (node (ref "J4") (pin "2") (pinfunction "2_2") (pintype "passive"))
    )
    (net (code "72") (name "unconnected-(J4-Pad3)") (class "Default")
      (node (ref "J4") (pin "3") (pinfunction "3_3") (pintype "passive"))
    )
    (net (code "73") (name "unconnected-(J4-Pad4)") (class "Default")
      (node (ref "J4") (pin "4") (pinfunction "4_4") (pintype "passive"))
    )
    (net (code "74") (name "unconnected-(J4-Pad5)") (class "Default")
      (node (ref "J4") (pin "5") (pinfunction "5_5") (pintype "passive"))
    )
    (net (code "75") (name "unconnected-(J4-Pad6)") (class "Default")
      (node (ref "J4") (pin "6") (pinfunction "6_6") (pintype "passive"))
    )
    (net (code "76") (name "unconnected-(J4-Pad7)") (class "Default")
      (node (ref "J4") (pin "7") (pinfunction "7_7") (pintype "passive"))
    )
    (net (code "77") (name "unconnected-(J4-Pad8)") (class "Default")
      (node (ref "J4") (pin "8") (pinfunction "8_8") (pintype "passive"))
    )
    (net (code "78") (name "unconnected-(J4-Pad9)") (class "Default")
      (node (ref "J4") (pin "9") (pinfunction "9_9") (pintype "passive"))
    )
    (net (code "79") (name "unconnected-(J4-Pad10)") (class "Default")
      (node (ref "J4") (pin "10") (pinfunction "10_10") (pintype "passive"))
    )
    (net (code "80") (name "unconnected-(J4-Pad11)") (class "Default")
      (node (ref "J4") (pin "11") (pinfunction "11_11") (pintype "passive"))
    )
    (net (code "81") (name "unconnected-(J4-Pad12)") (class "Default")
      (node (ref "J4") (pin "12") (pinfunction "12_12") (pintype "passive"))
    )
    (net (code "82") (name "unconnected-(J6-Pad1)") (class "Default")
      (node (ref "J6") (pin "1") (pinfunction "1_1") (pintype "passive"))
    )
    (net (code "83") (name "unconnected-(J6-Pad2)") (class "Default")
      (node (ref "J6") (pin "2") (pinfunction "2_2") (pintype "passive"))
    )
    (net (code "84") (name "unconnected-(J6-Pad3)") (class "Default")
      (node (ref "J6") (pin "3") (pinfunction "3_3") (pintype "passive"))
    )
    (net (code "85") (name "unconnected-(J6-Pad4)") (class "Default")
      (node (ref "J6") (pin "4") (pinfunction "4_4") (pintype "passive"))
    )
    (net (code "86") (name "unconnected-(J6-Pad5)") (class "Default")
      (node (ref "J6") (pin "5") (pinfunction "5_5") (pintype "passive"))
    )
    (net (code "87") (name "unconnected-(J6-Pad6)") (class "Default")
      (node (ref "J6") (pin "6") (pinfunction "6_6") (pintype "passive"))
    )
    (net (code "88") (name "unconnected-(J6-Pad7)") (class "Default")
      (node (ref "J6") (pin "7") (pinfunction "7_7") (pintype "passive"))
    )
    (net (code "89") (name "unconnected-(J6-Pad8)") (class "Default")
      (node (ref "J6") (pin "8") (pinfunction "8_8") (pintype "passive"))
    )
    (net (code "90") (name "unconnected-(J6-Pad9)") (class "Default")
      (node (ref "J6") (pin "9") (pinfunction "9_9") (pintype "passive"))
    )
    (net (code "91") (name "unconnected-(J6-Pad10)") (class "Default")
      (node (ref "J6") (pin "10") (pinfunction "10_10") (pintype "passive"))
    )
    (net (code "92") (name "unconnected-(J6-Pad11)") (class "Default")
      (node (ref "J6") (pin "11") (pinfunction "11_11") (pintype "passive"))
    )
    (net (code "93") (name "unconnected-(J6-Pad12)") (class "Default")
      (node (ref "J6") (pin "12") (pinfunction "12_12") (pintype "passive"))
    )
    (net (code "94") (name "unconnected-(J6-Pad13)") (class "Default")
      (node (ref "J6") (pin "13") (pinfunction "13_13") (pintype "passive"))
    )
    (net (code "95") (name "unconnected-(J6-Pad14)") (class "Default")
      (node (ref "J6") (pin "14") (pinfunction "14_14") (pintype "passive"))
    )
    (net (code "96") (name "unconnected-(J6-Pad15)") (class "Default")
      (node (ref "J6") (pin "15") (pinfunction "15_15") (pintype "passive"))
    )
    (net (code "97") (name "unconnected-(J6-Pad16)") (class "Default")
      (node (ref "J6") (pin "16") (pinfunction "16_16") (pintype "passive"))
    )
    (net (code "98") (name "unconnected-(J7-Pad1)") (class "Default")
      (node (ref "J7") (pin "1") (pinfunction "1_1") (pintype "passive"))
    )
    (net (code "99") (name "unconnected-(J7-Pad2)") (class "Default")
      (node (ref "J7") (pin "2") (pinfunction "2_2") (pintype "passive"))
    )
    (net (code "100") (name "unconnected-(J7-Pad3)") (class "Default")
      (node (ref "J7") (pin "3") (pinfunction "3_3") (pintype "passive"))
    )
    (net (code "101") (name "unconnected-(J7-Pad4)") (class "Default")
      (node (ref "J7") (pin "4") (pinfunction "4_4") (pintype "passive"))
    )
    (net (code "102") (name "unconnected-(J7-Pad5)") (class "Default")
      (node (ref "J7") (pin "5") (pinfunction "5_5") (pintype "passive"))
    )
    (net (code "103") (name "unconnected-(J7-Pad6)") (class "Default")
      (node (ref "J7") (pin "6") (pinfunction "6_6") (pintype "passive"))
    )
    (net (code "104") (name "unconnected-(J7-Pad7)") (class "Default")
      (node (ref "J7") (pin "7") (pinfunction "7_7") (pintype "passive"))
    )
    (net (code "105") (name "unconnected-(J7-Pad8)") (class "Default")
      (node (ref "J7") (pin "8") (pinfunction "8_8") (pintype "passive"))
    )
    (net (code "106") (name "unconnected-(J7-Pad9)") (class "Default")
      (node (ref "J7") (pin "9") (pinfunction "9_9") (pintype "passive"))
    )
    (net (code "107") (name "unconnected-(J7-Pad10)") (class "Default")
      (node (ref "J7") (pin "10") (pinfunction "10_10") (pintype "passive"))
    )
    (net (code "108") (name "unconnected-(J7-Pad11)") (class "Default")
      (node (ref "J7") (pin "11") (pinfunction "11_11") (pintype "passive"))
    )
    (net (code "109") (name "unconnected-(J7-Pad12)") (class "Default")
      (node (ref "J7") (pin "12") (pinfunction "12_12") (pintype "passive"))
    )
    (net (code "110") (name "unconnected-(J7-Pad13)") (class "Default")
      (node (ref "J7") (pin "13") (pinfunction "13_13") (pintype "passive"))
    )
    (net (code "111") (name "unconnected-(J7-Pad14)") (class "Default")
      (node (ref "J7") (pin "14") (pinfunction "14_14") (pintype "passive"))
    )
    (net (code "112") (name "unconnected-(J7-Pad15)") (class "Default")
      (node (ref "J7") (pin "15") (pinfunction "15_15") (pintype "passive"))
    )
    (net (code "113") (name "unconnected-(J7-Pad16)") (class "Default")
      (node (ref "J7") (pin "16") (pinfunction "16_16") (pintype "passive"))
    )
    (net (code "114") (name "unconnected-(J8-Pad1)") (class "Default")
      (node (ref "J8") (pin "1") (pinfunction "1_1") (pintype "passive"))
    )
    (net (code "115") (name "unconnected-(J8-Pad2)") (class "Default")
      (node (ref "J8") (pin "2") (pinfunction "2_2") (pintype "passive"))
    )
    (net (code "116") (name "unconnected-(J8-Pad3)") (class "Default")
      (node (ref "J8") (pin "3") (pinfunction "3_3") (pintype "passive"))
    )
    (net (code "117") (name "unconnected-(J8-Pad4)") (class "Default")
      (node (ref "J8") (pin "4") (pinfunction "4_4") (pintype "passive"))
    )
    (net (code "118") (name "unconnected-(J8-Pad5)") (class "Default")
      (node (ref "J8") (pin "5") (pinfunction "5_5") (pintype "passive"))
    )
    (net (code "119") (name "unconnected-(J8-Pad6)") (class "Default")
      (node (ref "J8") (pin "6") (pinfunction "6_6") (pintype "passive"))
    )
    (net (code "120") (name "unconnected-(J8-Pad7)") (class "Default")
      (node (ref "J8") (pin "7") (pinfunction "7_7") (pintype "passive"))
    )
    (net (code "121") (name "unconnected-(J8-Pad8)") (class "Default")
      (node (ref "J8") (pin "8") (pinfunction "8_8") (pintype "passive"))
    )
    (net (code "122") (name "unconnected-(J8-Pad9)") (class "Default")
      (node (ref "J8") (pin "9") (pinfunction "9_9") (pintype "passive"))
    )
    (net (code "123") (name "unconnected-(J8-Pad10)") (class "Default")
      (node (ref "J8") (pin "10") (pinfunction "10_10") (pintype "passive"))
    )
    (net (code "124") (name "unconnected-(J8-Pad11)") (class "Default")
      (node (ref "J8") (pin "11") (pinfunction "11_11") (pintype "passive"))
    )
    (net (code "125") (name "unconnected-(J8-Pad12)") (class "Default")
      (node (ref "J8") (pin "12") (pinfunction "12_12") (pintype "passive"))
    )
    (net (code "126") (name "unconnected-(J8-Pad13)") (class "Default")
      (node (ref "J8") (pin "13") (pinfunction "13_13") (pintype "passive"))
    )
    (net (code "127") (name "unconnected-(J8-Pad14)") (class "Default")
      (node (ref "J8") (pin "14") (pinfunction "14_14") (pintype "passive"))
    )
    (net (code "128") (name "unconnected-(J8-Pad15)") (class "Default")
      (node (ref "J8") (pin "15") (pinfunction "15_15") (pintype "passive"))
    )
    (net (code "129") (name "unconnected-(J8-Pad16)") (class "Default")
      (node (ref "J8") (pin "16") (pinfunction "16_16") (pintype "passive"))
    )
    (net (code "130") (name "unconnected-(J9-Pad1)") (class "Default")
      (node (ref "J9") (pin "1") (pinfunction "1_1") (pintype "passive"))
    )
    (net (code "131") (name "unconnected-(J10-Pad1)") (class "Default")
      (node (ref "J10") (pin "1") (pinfunction "1_1") (pintype "passive"))
    )
    (net (code "132") (name "unconnected-(J10-Pad2)") (class "Default")
      (node (ref "J10") (pin "2") (pinfunction "2_2") (pintype "passive"))
    )
    (net (code "133") (name "unconnected-(J10-Pad3)") (class "Default")
      (node (ref "J10") (pin "3") (pinfunction "3_3") (pintype "passive"))
    )
    (net (code "134") (name "unconnected-(J10-Pad4)") (class "Default")
      (node (ref "J10") (pin "4") (pinfunction "4_4") (pintype "passive"))
    )
    (net (code "135") (name "unconnected-(J10-Pad5)") (class "Default")
      (node (ref "J10") (pin "5") (pinfunction "5_5") (pintype "passive"))
    )
    (net (code "136") (name "unconnected-(J10-Pad6)") (class "Default")
      (node (ref "J10") (pin "6") (pinfunction "6_6") (pintype "passive"))
    )
    (net (code "137") (name "unconnected-(J10-Pad7)") (class "Default")
      (node (ref "J10") (pin "7") (pinfunction "7_7") (pintype "passive"))
    )
    (net (code "138") (name "unconnected-(J10-Pad8)") (class "Default")
      (node (ref "J10") (pin "8") (pinfunction "8_8") (pintype "passive"))
    )
    (net (code "139") (name "unconnected-(J10-Pad9)") (class "Default")
      (node (ref "J10") (pin "9") (pinfunction "9_9") (pintype "passive"))
    )
    (net (code "140") (name "unconnected-(J10-Pad10)") (class "Default")
      (node (ref "J10") (pin "10") (pinfunction "10_10") (pintype "passive"))
    )
    (net (code "141") (name "unconnected-(J10-Pad11)") (class "Default")
      (node (ref "J10") (pin "11") (pinfunction "11_11") (pintype "passive"))
    )
    (net (code "142") (name "unconnected-(J10-Pad12)") (class "Default")
      (node (ref "J10") (pin "12") (pinfunction "12_12") (pintype "passive"))
    )
    (net (code "143") (name "unconnected-(J10-Pad13)") (class "Default")
      (node (ref "J10") (pin "13") (pinfunction "13_13") (pintype "passive"))
    )
    (net (code "144") (name "unconnected-(J10-Pad14)") (class "Default")
      (node (ref "J10") (pin "14") (pinfunction "14_14") (pintype "passive"))
    )
    (net (code "145") (name "unconnected-(J10-Pad15)") (class "Default")
      (node (ref "J10") (pin "15") (pinfunction "15_15") (pintype "passive"))
    )
    (net (code "146") (name "unconnected-(J10-Pad16)") (class "Default")
      (node (ref "J10") (pin "16") (pinfunction "16_16") (pintype "passive"))
    )
    (net (code "147") (name "unconnected-(J12-Pad1)") (class "Default")
      (node (ref "J12") (pin "1") (pinfunction "1_1") (pintype "passive"))
    )
    (net (code "148") (name "unconnected-(J12-Pad2)") (class "Default")
      (node (ref "J12") (pin "2") (pinfunction "2_2") (pintype "passive"))
    )
    (net (code "149") (name "unconnected-(J12-Pad3)") (class "Default")
      (node (ref "J12") (pin "3") (pinfunction "3_3") (pintype "passive"))
    )
    (net (code "150") (name "unconnected-(J12-Pad4)") (class "Default")
      (node (ref "J12") (pin "4") (pinfunction "4_4") (pintype "passive"))
    )
    (net (code "151") (name "unconnected-(J12-Pad5)") (class "Default")
      (node (ref "J12") (pin "5") (pinfunction "5_5") (pintype "passive"))
    )
    (net (code "152") (name "unconnected-(J12-Pad6)") (class "Default")
      (node (ref "J12") (pin "6") (pinfunction "6_6") (pintype "passive"))
    )
    (net (code "153") (name "unconnected-(J12-Pad7)") (class "Default")
      (node (ref "J12") (pin "7") (pinfunction "7_7") (pintype "passive"))
    )
    (net (code "154") (name "unconnected-(J12-Pad8)") (class "Default")
      (node (ref "J12") (pin "8") (pinfunction "8_8") (pintype "passive"))
    )
    (net (code "155") (name "unconnected-(J12-Pad9)") (class "Default")
      (node (ref "J12") (pin "9") (pinfunction "9_9") (pintype "passive"))
    )
    (net (code "156") (name "unconnected-(J12-Pad10)") (class "Default")
      (node (ref "J12") (pin "10") (pinfunction "10_10") (pintype "passive"))
    )
    (net (code "157") (name "unconnected-(J12-Pad11)") (class "Default")
      (node (ref "J12") (pin "11") (pinfunction "11_11") (pintype "passive"))
    )
    (net (code "158") (name "unconnected-(J12-Pad12)") (class "Default")
      (node (ref "J12") (pin "12") (pinfunction "12_12") (pintype "passive"))
    )
    (net (code "159") (name "unconnected-(J12-Pad13)") (class "Default")
      (node (ref "J12") (pin "13") (pinfunction "13_13") (pintype "passive"))
    )
    (net (code "160") (name "unconnected-(J12-Pad14)") (class "Default")
      (node (ref "J12") (pin "14") (pinfunction "14_14") (pintype "passive"))
    )
    (net (code "161") (name "unconnected-(J12-Pad15)") (class "Default")
      (node (ref "J12") (pin "15") (pinfunction "15_15") (pintype "passive"))
    )
    (net (code "162") (name "unconnected-(J12-Pad16)") (class "Default")
      (node (ref "J12") (pin "16") (pinfunction "16_16") (pintype "passive"))
    )
    (net (code "163") (name "unconnected-(J13-Pad1)") (class "Default")
      (node (ref "J13") (pin "1") (pinfunction "1_1") (pintype "passive"))
    )
    (net (code "164") (name "unconnected-(J13-Pad2)") (class "Default")
      (node (ref "J13") (pin "2") (pinfunction "2_2") (pintype "passive"))
    )
    (net (code "165") (name "unconnected-(J13-Pad3)") (class "Default")
      (node (ref "J13") (pin "3") (pinfunction "3_3") (pintype "passive"))
    )
    (net (code "166") (name "unconnected-(J13-Pad4)") (class "Default")
      (node (ref "J13") (pin "4") (pinfunction "4_4") (pintype "passive"))
    )
    (net (code "167") (name "unconnected-(J13-Pad5)") (class "Default")
      (node (ref "J13") (pin "5") (pinfunction "5_5") (pintype "passive"))
    )
    (net (code "168") (name "unconnected-(J13-Pad6)") (class "Default")
      (node (ref "J13") (pin "6") (pinfunction "6_6") (pintype "passive"))
    )
    (net (code "169") (name "unconnected-(J13-Pad7)") (class "Default")
      (node (ref "J13") (pin "7") (pinfunction "7_7") (pintype "passive"))
    )
    (net (code "170") (name "unconnected-(J13-Pad8)") (class "Default")
      (node (ref "J13") (pin "8") (pinfunction "8_8") (pintype "passive"))
    )
    (net (code "171") (name "unconnected-(J13-Pad9)") (class "Default")
      (node (ref "J13") (pin "9") (pinfunction "9_9") (pintype "passive"))
    )
    (net (code "172") (name "unconnected-(J13-Pad10)") (class "Default")
      (node (ref "J13") (pin "10") (pinfunction "10_10") (pintype "passive"))
    )
    (net (code "173") (name "unconnected-(J13-Pad11)") (class "Default")
      (node (ref "J13") (pin "11") (pinfunction "11_11") (pintype "passive"))
    )
    (net (code "174") (name "unconnected-(J13-Pad12)") (class "Default")
      (node (ref "J13") (pin "12") (pinfunction "12_12") (pintype "passive"))
    )
    (net (code "175") (name "unconnected-(J13-Pad13)") (class "Default")
      (node (ref "J13") (pin "13") (pinfunction "13_13") (pintype "passive"))
    )
    (net (code "176") (name "unconnected-(J13-Pad14)") (class "Default")
      (node (ref "J13") (pin "14") (pinfunction "14_14") (pintype "passive"))
    )
    (net (code "177") (name "unconnected-(J13-Pad15)") (class "Default")
      (node (ref "J13") (pin "15") (pinfunction "15_15") (pintype "passive"))
    )
    (net (code "178") (name "unconnected-(J13-Pad16)") (class "Default")
      (node (ref "J13") (pin "16") (pinfunction "16_16") (pintype "passive"))
    )
    (net (code "179") (name "unconnected-(J14-Pad1)") (class "Default")
      (node (ref "J14") (pin "1") (pinfunction "1_1") (pintype "passive"))
    )
    (net (code "180") (name "unconnected-(J14-Pad2)") (class "Default")
      (node (ref "J14") (pin "2") (pinfunction "2_2") (pintype "passive"))
    )
    (net (code "181") (name "unconnected-(J14-Pad3)") (class "Default")
      (node (ref "J14") (pin "3") (pinfunction "3_3") (pintype "passive"))
    )
    (net (code "182") (name "unconnected-(J14-Pad4)") (class "Default")
      (node (ref "J14") (pin "4") (pinfunction "4_4") (pintype "passive"))
    )
    (net (code "183") (name "unconnected-(J14-Pad5)") (class "Default")
      (node (ref "J14") (pin "5") (pinfunction "5_5") (pintype "passive"))
    )
    (net (code "184") (name "unconnected-(J14-Pad6)") (class "Default")
      (node (ref "J14") (pin "6") (pinfunction "6_6") (pintype "passive"))
    )
    (net (code "185") (name "unconnected-(J14-Pad7)") (class "Default")
      (node (ref "J14") (pin "7") (pinfunction "7_7") (pintype "passive"))
    )
    (net (code "186") (name "unconnected-(J14-Pad8)") (class "Default")
      (node (ref "J14") (pin "8") (pinfunction "8_8") (pintype "passive"))
    )
    (net (code "187") (name "unconnected-(J14-Pad9)") (class "Default")
      (node (ref "J14") (pin "9") (pinfunction "9_9") (pintype "passive"))
    )
    (net (code "188") (name "unconnected-(J14-Pad10)") (class "Default")
      (node (ref "J14") (pin "10") (pinfunction "10_10") (pintype "passive"))
    )
    (net (code "189") (name "unconnected-(J14-Pad11)") (class "Default")
      (node (ref "J14") (pin "11") (pinfunction "11_11") (pintype "passive"))
    )
    (net (code "190") (name "unconnected-(J14-Pad12)") (class "Default")
      (node (ref "J14") (pin "12") (pinfunction "12_12") (pintype "passive"))
    )
    (net (code "191") (name "unconnected-(J14-Pad13)") (class "Default")
      (node (ref "J14") (pin "13") (pinfunction "13_13") (pintype "passive"))
    )
    (net (code "192") (name "unconnected-(J14-Pad14)") (class "Default")
      (node (ref "J14") (pin "14") (pinfunction "14_14") (pintype "passive"))
    )
    (net (code "193") (name "unconnected-(J14-Pad15)") (class "Default")
      (node (ref "J14") (pin "15") (pinfunction "15_15") (pintype "passive"))
    )
    (net (code "194") (name "unconnected-(J14-Pad16)") (class "Default")
      (node (ref "J14") (pin "16") (pinfunction "16_16") (pintype "passive"))
    )
    (net (code "195") (name "unconnected-(J15-Pad1)") (class "Default")
      (node (ref "J15") (pin "1") (pinfunction "1_1") (pintype "passive"))
    )
    (net (code "196") (name "unconnected-(J15-Pad2)") (class "Default")
      (node (ref "J15") (pin "2") (pinfunction "2_2") (pintype "passive"))
    )
    (net (code "197") (name "unconnected-(J15-Pad3)") (class "Default")
      (node (ref "J15") (pin "3") (pinfunction "3_3") (pintype "passive"))
    )
    (net (code "198") (name "unconnected-(J15-Pad4)") (class "Default")
      (node (ref "J15") (pin "4") (pinfunction "4_4") (pintype "passive"))
    )
    (net (code "199") (name "unconnected-(J15-Pad5)") (class "Default")
      (node (ref "J15") (pin "5") (pinfunction "5_5") (pintype "passive"))
    )
    (net (code "200") (name "unconnected-(J15-Pad6)") (class "Default")
      (node (ref "J15") (pin "6") (pinfunction "6_6") (pintype "passive"))
    )
    (net (code "201") (name "unconnected-(J15-Pad7)") (class "Default")
      (node (ref "J15") (pin "7") (pinfunction "7_7") (pintype "passive"))
    )
    (net (code "202") (name "unconnected-(J15-Pad8)") (class "Default")
      (node (ref "J15") (pin "8") (pinfunction "8_8") (pintype "passive"))
    )
    (net (code "203") (name "unconnected-(J15-Pad9)") (class "Default")
      (node (ref "J15") (pin "9") (pinfunction "9_9") (pintype "passive"))
    )
    (net (code "204") (name "unconnected-(J15-Pad10)") (class "Default")
      (node (ref "J15") (pin "10") (pinfunction "10_10") (pintype "passive"))
    )
    (net (code "205") (name "unconnected-(J15-Pad11)") (class "Default")
      (node (ref "J15") (pin "11") (pinfunction "11_11") (pintype "passive"))
    )
    (net (code "206") (name "unconnected-(J15-Pad12)") (class "Default")
      (node (ref "J15") (pin "12") (pinfunction "12_12") (pintype "passive"))
    )
    (net (code "207") (name "unconnected-(J15-Pad13)") (class "Default")
      (node (ref "J15") (pin "13") (pinfunction "13_13") (pintype "passive"))
    )
    (net (code "208") (name "unconnected-(J15-Pad14)") (class "Default")
      (node (ref "J15") (pin "14") (pinfunction "14_14") (pintype "passive"))
    )
    (net (code "209") (name "unconnected-(J15-Pad15)") (class "Default")
      (node (ref "J15") (pin "15") (pinfunction "15_15") (pintype "passive"))
    )
    (net (code "210") (name "unconnected-(J15-Pad16)") (class "Default")
      (node (ref "J15") (pin "16") (pinfunction "16_16") (pintype "passive"))
    )
    (net (code "211") (name "unconnected-(J16-Pad1)") (class "Default")
      (node (ref "J16") (pin "1") (pinfunction "1_1") (pintype "passive"))
    )
    (net (code "212") (name "unconnected-(J16-Pad2)") (class "Default")
      (node (ref "J16") (pin "2") (pinfunction "2_2") (pintype "passive"))
    )
    (net (code "213") (name "unconnected-(J16-Pad3)") (class "Default")
      (node (ref "J16") (pin "3") (pinfunction "3_3") (pintype "passive"))
    )
    (net (code "214") (name "unconnected-(J16-Pad4)") (class "Default")
      (node (ref "J16") (pin "4") (pinfunction "4_4") (pintype "passive"))
    )
    (net (code "215") (name "unconnected-(J16-Pad5)") (class "Default")
      (node (ref "J16") (pin "5") (pinfunction "5_5") (pintype "passive"))
    )
    (net (code "216") (name "unconnected-(J16-Pad6)") (class "Default")
      (node (ref "J16") (pin "6") (pinfunction "6_6") (pintype "passive"))
    )
    (net (code "217") (name "unconnected-(J16-Pad7)") (class "Default")
      (node (ref "J16") (pin "7") (pinfunction "7_7") (pintype "passive"))
    )
    (net (code "218") (name "unconnected-(J16-Pad8)") (class "Default")
      (node (ref "J16") (pin "8") (pinfunction "8_8") (pintype "passive"))
    )
    (net (code "219") (name "unconnected-(J16-Pad9)") (class "Default")
      (node (ref "J16") (pin "9") (pinfunction "9_9") (pintype "passive"))
    )
    (net (code "220") (name "unconnected-(J16-Pad10)") (class "Default")
      (node (ref "J16") (pin "10") (pinfunction "10_10") (pintype "passive"))
    )
    (net (code "221") (name "unconnected-(J16-Pad11)") (class "Default")
      (node (ref "J16") (pin "11") (pinfunction "11_11") (pintype "passive"))
    )
    (net (code "222") (name "unconnected-(J16-Pad12)") (class "Default")
      (node (ref "J16") (pin "12") (pinfunction "12_12") (pintype "passive"))
    )
    (net (code "223") (name "unconnected-(J16-Pad13)") (class "Default")
      (node (ref "J16") (pin "13") (pinfunction "13_13") (pintype "passive"))
    )
    (net (code "224") (name "unconnected-(J16-Pad14)") (class "Default")
      (node (ref "J16") (pin "14") (pinfunction "14_14") (pintype "passive"))
    )
    (net (code "225") (name "unconnected-(J16-Pad15)") (class "Default")
      (node (ref "J16") (pin "15") (pinfunction "15_15") (pintype "passive"))
    )
    (net (code "226") (name "unconnected-(J16-Pad16)") (class "Default")
      (node (ref "J16") (pin "16") (pinfunction "16_16") (pintype "passive"))
    )
    (net (code "227") (name "unconnected-(J17-Pad1)") (class "Default")
      (node (ref "J17") (pin "1") (pinfunction "1_1") (pintype "passive"))
    )
    (net (code "228") (name "unconnected-(J17-Pad2)") (class "Default")
      (node (ref "J17") (pin "2") (pinfunction "2_2") (pintype "passive"))
    )
    (net (code "229") (name "unconnected-(J17-Pad3)") (class "Default")
      (node (ref "J17") (pin "3") (pinfunction "3_3") (pintype "passive"))
    )
    (net (code "230") (name "unconnected-(J17-Pad4)") (class "Default")
      (node (ref "J17") (pin "4") (pinfunction "4_4") (pintype "passive"))
    )
    (net (code "231") (name "unconnected-(J17-Pad5)") (class "Default")
      (node (ref "J17") (pin "5") (pinfunction "5_5") (pintype "passive"))
    )
    (net (code "232") (name "unconnected-(J17-Pad6)") (class "Default")
      (node (ref "J17") (pin "6") (pinfunction "6_6") (pintype "passive"))
    )
    (net (code "233") (name "unconnected-(J17-Pad7)") (class "Default")
      (node (ref "J17") (pin "7") (pinfunction "7_7") (pintype "passive"))
    )
    (net (code "234") (name "unconnected-(J17-Pad8)") (class "Default")
      (node (ref "J17") (pin "8") (pinfunction "8_8") (pintype "passive"))
    )
    (net (code "235") (name "unconnected-(J17-Pad9)") (class "Default")
      (node (ref "J17") (pin "9") (pinfunction "9_9") (pintype "passive"))
    )
    (net (code "236") (name "unconnected-(J17-Pad10)") (class "Default")
      (node (ref "J17") (pin "10") (pinfunction "10_10") (pintype "passive"))
    )
    (net (code "237") (name "unconnected-(J17-Pad11)") (class "Default")
      (node (ref "J17") (pin "11") (pinfunction "11_11") (pintype "passive"))
    )
    (net (code "238") (name "unconnected-(J17-Pad12)") (class "Default")
      (node (ref "J17") (pin "12") (pinfunction "12_12") (pintype "passive"))
    )
    (net (code "239") (name "unconnected-(J17-Pad13)") (class "Default")
      (node (ref "J17") (pin "13") (pinfunction "13_13") (pintype "passive"))
    )
    (net (code "240") (name "unconnected-(J17-Pad14)") (class "Default")
      (node (ref "J17") (pin "14") (pinfunction "14_14") (pintype "passive"))
    )
    (net (code "241") (name "unconnected-(J17-Pad15)") (class "Default")
      (node (ref "J17") (pin "15") (pinfunction "15_15") (pintype "passive"))
    )
    (net (code "242") (name "unconnected-(J17-Pad16)") (class "Default")
      (node (ref "J17") (pin "16") (pinfunction "16_16") (pintype "passive"))
    )
    (net (code "243") (name "unconnected-(J18-Pad1)") (class "Default")
      (node (ref "J18") (pin "1") (pinfunction "1_1") (pintype "passive"))
    )
    (net (code "244") (name "unconnected-(J18-Pad2)") (class "Default")
      (node (ref "J18") (pin "2") (pinfunction "2_2") (pintype "passive"))
    )
    (net (code "245") (name "unconnected-(J18-Pad3)") (class "Default")
      (node (ref "J18") (pin "3") (pinfunction "3_3") (pintype "passive"))
    )
    (net (code "246") (name "unconnected-(J18-Pad4)") (class "Default")
      (node (ref "J18") (pin "4") (pinfunction "4_4") (pintype "passive"))
    )
    (net (code "247") (name "unconnected-(J18-Pad5)") (class "Default")
      (node (ref "J18") (pin "5") (pinfunction "5_5") (pintype "passive"))
    )
    (net (code "248") (name "unconnected-(J18-Pad6)") (class "Default")
      (node (ref "J18") (pin "6") (pinfunction "6_6") (pintype "passive"))
    )
    (net (code "249") (name "unconnected-(J18-Pad7)") (class "Default")
      (node (ref "J18") (pin "7") (pinfunction "7_7") (pintype "passive"))
    )
    (net (code "250") (name "unconnected-(J18-Pad8)") (class "Default")
      (node (ref "J18") (pin "8") (pinfunction "8_8") (pintype "passive"))
    )
    (net (code "251") (name "unconnected-(J18-Pad9)") (class "Default")
      (node (ref "J18") (pin "9") (pinfunction "9_9") (pintype "passive"))
    )
    (net (code "252") (name "unconnected-(J18-Pad10)") (class "Default")
      (node (ref "J18") (pin "10") (pinfunction "10_10") (pintype "passive"))
    )
    (net (code "253") (name "unconnected-(J18-Pad11)") (class "Default")
      (node (ref "J18") (pin "11") (pinfunction "11_11") (pintype "passive"))
    )
    (net (code "254") (name "unconnected-(J18-Pad12)") (class "Default")
      (node (ref "J18") (pin "12") (pinfunction "12_12") (pintype "passive"))
    )
    (net (code "255") (name "unconnected-(J18-Pad13)") (class "Default")
      (node (ref "J18") (pin "13") (pinfunction "13_13") (pintype "passive"))
    )
    (net (code "256") (name "unconnected-(J18-Pad14)") (class "Default")
      (node (ref "J18") (pin "14") (pinfunction "14_14") (pintype "passive"))
    )
    (net (code "257") (name "unconnected-(J18-Pad15)") (class "Default")
      (node (ref "J18") (pin "15") (pinfunction "15_15") (pintype "passive"))
    )
    (net (code "258") (name "unconnected-(J18-Pad16)") (class "Default")
      (node (ref "J18") (pin "16") (pinfunction "16_16") (pintype "passive"))
    )
    (net (code "259") (name "unconnected-(J19-Pad1)") (class "Default")
      (node (ref "J19") (pin "1") (pinfunction "1_1") (pintype "passive"))
    )
    (net (code "260") (name "unconnected-(J19-Pad2)") (class "Default")
      (node (ref "J19") (pin "2") (pinfunction "2_2") (pintype "passive"))
    )
    (net (code "261") (name "unconnected-(J19-Pad3)") (class "Default")
      (node (ref "J19") (pin "3") (pinfunction "3_3") (pintype "passive"))
    )
    (net (code "262") (name "unconnected-(J19-Pad4)") (class "Default")
      (node (ref "J19") (pin "4") (pinfunction "4_4") (pintype "passive"))
    )
    (net (code "263") (name "unconnected-(J19-Pad5)") (class "Default")
      (node (ref "J19") (pin "5") (pinfunction "5_5") (pintype "passive"))
    )
    (net (code "264") (name "unconnected-(J19-Pad6)") (class "Default")
      (node (ref "J19") (pin "6") (pinfunction "6_6") (pintype "passive"))
    )
    (net (code "265") (name "unconnected-(J19-Pad7)") (class "Default")
      (node (ref "J19") (pin "7") (pinfunction "7_7") (pintype "passive"))
    )
    (net (code "266") (name "unconnected-(J19-Pad8)") (class "Default")
      (node (ref "J19") (pin "8") (pinfunction "8_8") (pintype "passive"))
    )
    (net (code "267") (name "unconnected-(J19-Pad9)") (class "Default")
      (node (ref "J19") (pin "9") (pinfunction "9_9") (pintype "passive"))
    )
    (net (code "268") (name "unconnected-(J19-Pad10)") (class "Default")
      (node (ref "J19") (pin "10") (pinfunction "10_10") (pintype "passive"))
    )
    (net (code "269") (name "unconnected-(J19-Pad11)") (class "Default")
      (node (ref "J19") (pin "11") (pinfunction "11_11") (pintype "passive"))
    )
    (net (code "270") (name "unconnected-(J19-Pad12)") (class "Default")
      (node (ref "J19") (pin "12") (pinfunction "12_12") (pintype "passive"))
    )
    (net (code "271") (name "unconnected-(J19-Pad13)") (class "Default")
      (node (ref "J19") (pin "13") (pinfunction "13_13") (pintype "passive"))
    )
    (net (code "272") (name "unconnected-(J19-Pad14)") (class "Default")
      (node (ref "J19") (pin "14") (pinfunction "14_14") (pintype "passive"))
    )
    (net (code "273") (name "unconnected-(J19-Pad15)") (class "Default")
      (node (ref "J19") (pin "15") (pinfunction "15_15") (pintype "passive"))
    )
    (net (code "274") (name "unconnected-(J19-Pad16)") (class "Default")
      (node (ref "J19") (pin "16") (pinfunction "16_16") (pintype "passive"))
    )
    (net (code "275") (name "unconnected-(J20-Pad1)") (class "Default")
      (node (ref "J20") (pin "1") (pinfunction "1_1") (pintype "passive"))
    )
    (net (code "276") (name "unconnected-(J20-Pad2)") (class "Default")
      (node (ref "J20") (pin "2") (pinfunction "2_2") (pintype "passive"))
    )
    (net (code "277") (name "unconnected-(J20-Pad3)") (class "Default")
      (node (ref "J20") (pin "3") (pinfunction "3_3") (pintype "passive"))
    )
    (net (code "278") (name "unconnected-(J20-Pad4)") (class "Default")
      (node (ref "J20") (pin "4") (pinfunction "4_4") (pintype "passive"))
    )
    (net (code "279") (name "unconnected-(J20-Pad5)") (class "Default")
      (node (ref "J20") (pin "5") (pinfunction "5_5") (pintype "passive"))
    )
    (net (code "280") (name "unconnected-(J20-Pad6)") (class "Default")
      (node (ref "J20") (pin "6") (pinfunction "6_6") (pintype "passive"))
    )
    (net (code "281") (name "unconnected-(J20-Pad7)") (class "Default")
      (node (ref "J20") (pin "7") (pinfunction "7_7") (pintype "passive"))
    )
    (net (code "282") (name "unconnected-(J20-Pad8)") (class "Default")
      (node (ref "J20") (pin "8") (pinfunction "8_8") (pintype "passive"))
    )
    (net (code "283") (name "unconnected-(J20-Pad9)") (class "Default")
      (node (ref "J20") (pin "9") (pinfunction "9_9") (pintype "passive"))
    )
    (net (code "284") (name "unconnected-(J20-Pad10)") (class "Default")
      (node (ref "J20") (pin "10") (pinfunction "10_10") (pintype "passive"))
    )
    (net (code "285") (name "unconnected-(J20-Pad11)") (class "Default")
      (node (ref "J20") (pin "11") (pinfunction "11_11") (pintype "passive"))
    )
    (net (code "286") (name "unconnected-(J20-Pad12)") (class "Default")
      (node (ref "J20") (pin "12") (pinfunction "12_12") (pintype "passive"))
    )
    (net (code "287") (name "unconnected-(J20-Pad13)") (class "Default")
      (node (ref "J20") (pin "13") (pinfunction "13_13") (pintype "passive"))
    )
    (net (code "288") (name "unconnected-(J20-Pad14)") (class "Default")
      (node (ref "J20") (pin "14") (pinfunction "14_14") (pintype "passive"))
    )
    (net (code "289") (name "unconnected-(J20-Pad15)") (class "Default")
      (node (ref "J20") (pin "15") (pinfunction "15_15") (pintype "passive"))
    )
    (net (code "290") (name "unconnected-(J20-Pad16)") (class "Default")
      (node (ref "J20") (pin "16") (pinfunction "16_16") (pintype "passive"))
    )
    (net (code "291") (name "unconnected-(J21-Pad1)") (class "Default")
      (node (ref "J21") (pin "1") (pinfunction "1_1") (pintype "passive"))
    )
    (net (code "292") (name "unconnected-(J21-Pad2)") (class "Default")
      (node (ref "J21") (pin "2") (pinfunction "2_2") (pintype "passive"))
    )
    (net (code "293") (name "unconnected-(J21-Pad3)") (class "Default")
      (node (ref "J21") (pin "3") (pinfunction "3_3") (pintype "passive"))
    )
    (net (code "294") (name "unconnected-(J21-Pad4)") (class "Default")
      (node (ref "J21") (pin "4") (pinfunction "4_4") (pintype "passive"))
    )
    (net (code "295") (name "unconnected-(J21-Pad5)") (class "Default")
      (node (ref "J21") (pin "5") (pinfunction "5_5") (pintype "passive"))
    )
    (net (code "296") (name "unconnected-(J21-Pad6)") (class "Default")
      (node (ref "J21") (pin "6") (pinfunction "6_6") (pintype "passive"))
    )
    (net (code "297") (name "unconnected-(J21-Pad7)") (class "Default")
      (node (ref "J21") (pin "7") (pinfunction "7_7") (pintype "passive"))
    )
    (net (code "298") (name "unconnected-(J21-Pad8)") (class "Default")
      (node (ref "J21") (pin "8") (pinfunction "8_8") (pintype "passive"))
    )
    (net (code "299") (name "unconnected-(J21-Pad9)") (class "Default")
      (node (ref "J21") (pin "9") (pinfunction "9_9") (pintype "passive"))
    )
    (net (code "300") (name "unconnected-(J21-Pad10)") (class "Default")
      (node (ref "J21") (pin "10") (pinfunction "10_10") (pintype "passive"))
    )
    (net (code "301") (name "unconnected-(J21-Pad11)") (class "Default")
      (node (ref "J21") (pin "11") (pinfunction "11_11") (pintype "passive"))
    )
    (net (code "302") (name "unconnected-(J21-Pad12)") (class "Default")
      (node (ref "J21") (pin "12") (pinfunction "12_12") (pintype "passive"))
    )
    (net (code "303") (name "unconnected-(J21-Pad13)") (class "Default")
      (node (ref "J21") (pin "13") (pinfunction "13_13") (pintype "passive"))
    )
    (net (code "304") (name "unconnected-(J21-Pad14)") (class "Default")
      (node (ref "J21") (pin "14") (pinfunction "14_14") (pintype "passive"))
    )
    (net (code "305") (name "unconnected-(J21-Pad15)") (class "Default")
      (node (ref "J21") (pin "15") (pinfunction "15_15") (pintype "passive"))
    )
    (net (code "306") (name "unconnected-(J21-Pad16)") (class "Default")
      (node (ref "J21") (pin "16") (pinfunction "16_16") (pintype "passive"))
    )
    (net (code "307") (name "unconnected-(J22-Pad1)") (class "Default")
      (node (ref "J22") (pin "1") (pinfunction "1_1") (pintype "passive"))
    )
    (net (code "308") (name "unconnected-(J22-Pad2)") (class "Default")
      (node (ref "J22") (pin "2") (pinfunction "2_2") (pintype "passive"))
    )
    (net (code "309") (name "unconnected-(J22-Pad3)") (class "Default")
      (node (ref "J22") (pin "3") (pinfunction "3_3") (pintype "passive"))
    )
    (net (code "310") (name "unconnected-(J22-Pad4)") (class "Default")
      (node (ref "J22") (pin "4") (pinfunction "4_4") (pintype "passive"))
    )
    (net (code "311") (name "unconnected-(J22-Pad5)") (class "Default")
      (node (ref "J22") (pin "5") (pinfunction "5_5") (pintype "passive"))
    )
    (net (code "312") (name "unconnected-(J22-Pad6)") (class "Default")
      (node (ref "J22") (pin "6") (pinfunction "6_6") (pintype "passive"))
    )
    (net (code "313") (name "unconnected-(J22-Pad7)") (class "Default")
      (node (ref "J22") (pin "7") (pinfunction "7_7") (pintype "passive"))
    )
    (net (code "314") (name "unconnected-(J22-Pad8)") (class "Default")
      (node (ref "J22") (pin "8") (pinfunction "8_8") (pintype "passive"))
    )
    (net (code "315") (name "unconnected-(J22-Pad9)") (class "Default")
      (node (ref "J22") (pin "9") (pinfunction "9_9") (pintype "passive"))
    )
    (net (code "316") (name "unconnected-(J22-Pad10)") (class "Default")
      (node (ref "J22") (pin "10") (pinfunction "10_10") (pintype "passive"))
    )
    (net (code "317") (name "unconnected-(J22-Pad11)") (class "Default")
      (node (ref "J22") (pin "11") (pinfunction "11_11") (pintype "passive"))
    )
    (net (code "318") (name "unconnected-(J22-Pad12)") (class "Default")
      (node (ref "J22") (pin "12") (pinfunction "12_12") (pintype "passive"))
    )
    (net (code "319") (name "unconnected-(J22-Pad13)") (class "Default")
      (node (ref "J22") (pin "13") (pinfunction "13_13") (pintype "passive"))
    )
    (net (code "320") (name "unconnected-(J22-Pad14)") (class "Default")
      (node (ref "J22") (pin "14") (pinfunction "14_14") (pintype "passive"))
    )
    (net (code "321") (name "unconnected-(J22-Pad15)") (class "Default")
      (node (ref "J22") (pin "15") (pinfunction "15_15") (pintype "passive"))
    )
    (net (code "322") (name "unconnected-(J22-Pad16)") (class "Default")
      (node (ref "J22") (pin "16") (pinfunction "16_16") (pintype "passive"))
    )
    (net (code "323") (name "unconnected-(J25-Pad1)") (class "Default")
      (node (ref "J25") (pin "1") (pinfunction "1_1") (pintype "passive"))
    )
    (net (code "324") (name "unconnected-(JP1-PadD+)") (class "Default")
      (node (ref "JP1") (pin "D+") (pinfunction "D+_D+") (pintype "bidirectional"))
    )
    (net (code "325") (name "unconnected-(JP1-PadD-)") (class "Default")
      (node (ref "JP1") (pin "D-") (pinfunction "D-_D-") (pintype "bidirectional"))
    )
  )
)
